# Adafruit_SHT4x_Trinkey.net
KiCad netlist of a schematic drawn in EAGLE
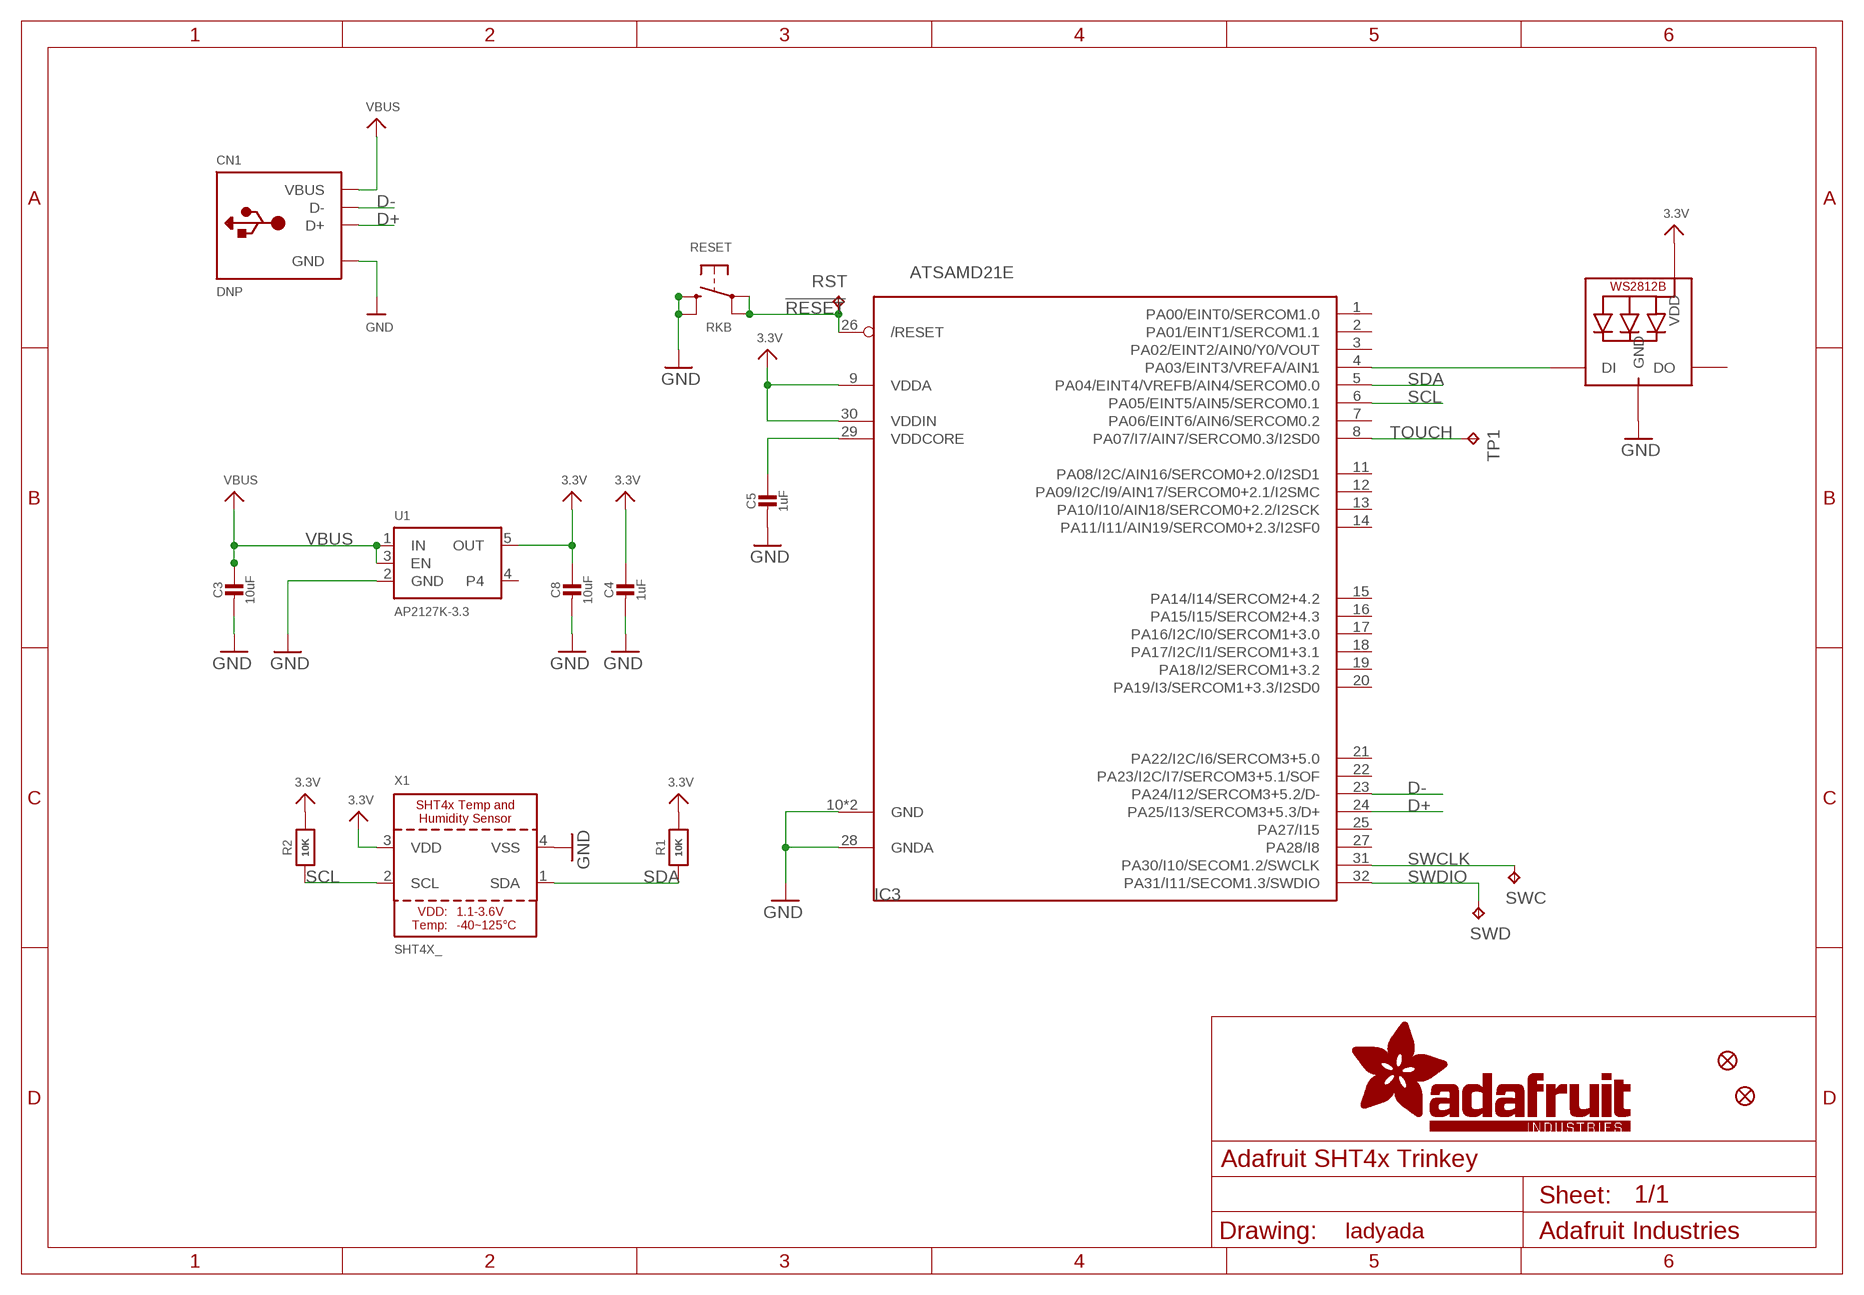
[diagram p0: schematic, sheet 1]

(export (version "E")
  (design (tool "Eeschema 10.0.6"))
  (components
    (comp (ref "C3")
      (value "10uF")
      (footprint "eagle-import:0805-NO")
      (libsource (lib "eagle-import") (part "CAP_CERAMIC0805-NOOUTLINE"))
    )
    (comp (ref "C4")
      (value "1uF")
      (footprint "eagle-import:_0603MP")
      (libsource (lib "eagle-import") (part "CAP_CERAMIC_0603MP"))
    )
    (comp (ref "C5")
      (value "1uF")
      (footprint "eagle-import:0603-NO")
      (libsource (lib "eagle-import") (part "CAP_CERAMIC0603_NO"))
    )
    (comp (ref "C8")
      (value "10uF")
      (footprint "eagle-import:0805-NO")
      (libsource (lib "eagle-import") (part "CAP_CERAMIC0805-NOOUTLINE"))
    )
    (comp (ref "CN1")
      (value "DNP")
      (footprint "eagle-import:USBA_PCB")
      (libsource (lib "eagle-import") (part "USB_TYPEAPCB"))
    )
    (comp (ref "FID1")
      (value "FIDUCIAL_0.5MM")
      (footprint "eagle-import:FIDUCIAL_0.5MM")
      (libsource (lib "eagle-import") (part "FIDUCIAL_0.5MM"))
    )
    (comp (ref "FID2")
      (value "FIDUCIAL_0.5MM")
      (footprint "eagle-import:FIDUCIAL_0.5MM")
      (libsource (lib "eagle-import") (part "FIDUCIAL_0.5MM"))
    )
    (comp (ref "IC3")
      (value "ATSAMD21E")
      (footprint "eagle-import:QFN32_5MM")
      (libsource (lib "eagle-import") (part "ATSAMD21E"))
    )
    (comp (ref "LED1")
      (value "WS2812B_SK6805_1515")
      (footprint "eagle-import:SK6805_1515")
      (libsource (lib "eagle-import") (part "WS2812B_SK6805_1515"))
    )
    (comp (ref "R1")
      (value "10K")
      (footprint "eagle-import:_0402NO")
      (libsource (lib "eagle-import") (part "RESISTOR_0402NO"))
    )
    (comp (ref "R2")
      (value "10K")
      (footprint "eagle-import:_0402NO")
      (libsource (lib "eagle-import") (part "RESISTOR_0402NO"))
    )
    (comp (ref "RESET")
      (value "RKB")
      (footprint "eagle-import:BTN_RKB2_4.6X2.8")
      (libsource (lib "eagle-import") (part "SWITCH_TACT_SMT_RKB2"))
    )
    (comp (ref "RST")
      (value "TPTP16R")
      (footprint "eagle-import:TP16R")
      (libsource (lib "eagle-import") (part "TPTP16R"))
    )
    (comp (ref "SWC")
      (value "TPTP15R")
      (footprint "eagle-import:TP15R")
      (libsource (lib "eagle-import") (part "TPTP15R"))
    )
    (comp (ref "SWD")
      (value "TPTP16R")
      (footprint "eagle-import:TP16R")
      (libsource (lib "eagle-import") (part "TPTP16R"))
    )
    (comp (ref "TP1")
      (value "DNP")
      (footprint "eagle-import:TP13R")
      (libsource (lib "eagle-import") (part "TPTP13R"))
    )
    (comp (ref "U1")
      (value "AP2127K-3.3")
      (footprint "eagle-import:SOT23-5")
      (fields (field (name "JLC_ROTATION") "0"))
      (libsource (lib "eagle-import") (part "VREG_SOT23-5"))
    )
    (comp (ref "X1")
      (value "SHT4X_")
      (footprint "eagle-import:SHT4X")
      (libsource (lib "eagle-import") (part "SHT4X_"))
    )
  )
  (nets
    (net (code "1") (name "/D+") (class "Default")
      (node (ref "CN1") (pin "USB_PLUS") (pinfunction "D+_USB_PLUS") (pintype "bidirectional"))
      (node (ref "IC3") (pin "24") (pinfunction "PA25/I13/SERCOM3+5.3/D+_24") (pintype "bidirectional"))
    )
    (net (code "2") (name "/D-") (class "Default")
      (node (ref "CN1") (pin "USB_NEG") (pinfunction "D-_USB_NEG") (pintype "bidirectional"))
      (node (ref "IC3") (pin "23") (pinfunction "PA24/I12/SERCOM3+5.2/D-_23") (pintype "bidirectional"))
    )
    (net (code "3") (name "/SCL") (class "Default")
      (node (ref "IC3") (pin "6") (pinfunction "PA05/EINT5/AIN5/SERCOM0.1_6") (pintype "bidirectional"))
      (node (ref "R2") (pin "1") (pinfunction "1_1") (pintype "passive"))
      (node (ref "X1") (pin "2") (pinfunction "SCL_2") (pintype "bidirectional"))
    )
    (net (code "4") (name "/SDA") (class "Default")
      (node (ref "IC3") (pin "5") (pinfunction "PA04/EINT4/VREFB/AIN4/SERCOM0.0_5") (pintype "bidirectional"))
      (node (ref "R1") (pin "1") (pinfunction "1_1") (pintype "passive"))
      (node (ref "X1") (pin "1") (pinfunction "SDA_1") (pintype "bidirectional"))
    )
    (net (code "5") (name "/SWCLK") (class "Default")
      (node (ref "IC3") (pin "31") (pinfunction "PA30/I10/SECOM1.2/SWCLK_31") (pintype "bidirectional"))
      (node (ref "SWC") (pin "TP") (pinfunction "TP_TP") (pintype "input"))
    )
    (net (code "6") (name "/SWDIO") (class "Default")
      (node (ref "IC3") (pin "32") (pinfunction "PA31/I11/SECOM1.3/SWDIO_32") (pintype "bidirectional"))
      (node (ref "SWD") (pin "TP") (pinfunction "TP_TP") (pintype "input"))
    )
    (net (code "7") (name "/TOUCH") (class "Default")
      (node (ref "IC3") (pin "8") (pinfunction "PA07/I7/AIN7/SERCOM0.3/I2SD0_8") (pintype "bidirectional"))
      (node (ref "TP1") (pin "TP") (pinfunction "TP_TP") (pintype "input"))
    )
    (net (code "8") (name "/~{RESET}") (class "Default")
      (node (ref "IC3") (pin "26") (pinfunction "/RESET_26") (pintype "bidirectional"))
      (node (ref "RESET") (pin "A") (pinfunction "P_A") (pintype "passive"))
      (node (ref "RESET") (pin "A'") (pinfunction "P1_A'") (pintype "passive"))
      (node (ref "RST") (pin "TP") (pinfunction "TP_TP") (pintype "input"))
    )
    (net (code "9") (name "3.3V") (class "Default")
      (node (ref "C4") (pin "1") (pinfunction "1_1") (pintype "passive"))
      (node (ref "C8") (pin "1") (pinfunction "1_1") (pintype "passive"))
      (node (ref "IC3") (pin "30") (pinfunction "VDDIN_30") (pintype "power_in"))
      (node (ref "IC3") (pin "9") (pinfunction "VDDA_9") (pintype "power_in"))
      (node (ref "LED1") (pin "2") (pinfunction "VDD_2") (pintype "power_in"))
      (node (ref "R1") (pin "2") (pinfunction "2_2") (pintype "passive"))
      (node (ref "R2") (pin "2") (pinfunction "2_2") (pintype "passive"))
      (node (ref "U1") (pin "5") (pinfunction "OUT_5") (pintype "power_in"))
      (node (ref "X1") (pin "3") (pinfunction "VDD_3") (pintype "power_in"))
    )
    (net (code "10") (name "GND") (class "Default")
      (node (ref "C3") (pin "2") (pinfunction "2_2") (pintype "passive"))
      (node (ref "C4") (pin "2") (pinfunction "2_2") (pintype "passive"))
      (node (ref "C5") (pin "2") (pinfunction "2_2") (pintype "passive"))
      (node (ref "C8") (pin "2") (pinfunction "2_2") (pintype "passive"))
      (node (ref "CN1") (pin "GND") (pinfunction "GND_GND") (pintype "power_in"))
      (node (ref "IC3") (pin "10") (pinfunction "GND_10") (pintype "power_in"))
      (node (ref "IC3") (pin "28") (pinfunction "GNDA_28") (pintype "power_in"))
      (node (ref "IC3") (pin "33") (pinfunction "GND_33") (pintype "power_in"))
      (node (ref "LED1") (pin "4") (pinfunction "GND_4") (pintype "power_in"))
      (node (ref "RESET") (pin "B") (pinfunction "S_B") (pintype "passive"))
      (node (ref "RESET") (pin "B'") (pinfunction "S1_B'") (pintype "passive"))
      (node (ref "U1") (pin "2") (pinfunction "GND_2") (pintype "power_in"))
      (node (ref "X1") (pin "4") (pinfunction "VSS_4") (pintype "power_in"))
    )
    (net (code "11") (name "Net-(IC3-PA03{slash}EINT3{slash}VREFA{slash}AIN1)") (class "Default")
      (node (ref "IC3") (pin "4") (pinfunction "PA03/EINT3/VREFA/AIN1_4") (pintype "bidirectional"))
      (node (ref "LED1") (pin "1") (pinfunction "DI_1") (pintype "input"))
    )
    (net (code "12") (name "Net-(IC3-VDDCORE)") (class "Default")
      (node (ref "C5") (pin "1") (pinfunction "1_1") (pintype "passive"))
      (node (ref "IC3") (pin "29") (pinfunction "VDDCORE_29") (pintype "power_in"))
    )
    (net (code "13") (name "VBUS") (class "Default")
      (node (ref "C3") (pin "1") (pinfunction "1_1") (pintype "passive"))
      (node (ref "CN1") (pin "VCC") (pinfunction "VBUS_VCC") (pintype "power_in"))
      (node (ref "U1") (pin "1") (pinfunction "IN_1") (pintype "power_in"))
      (node (ref "U1") (pin "3") (pinfunction "EN_3") (pintype "input"))
    )
    (net (code "14") (name "unconnected-(IC3-PA00{slash}EINT0{slash}SERCOM1.0-Pad1)") (class "Default")
      (node (ref "IC3") (pin "1") (pinfunction "PA00/EINT0/SERCOM1.0_1") (pintype "bidirectional"))
    )
    (net (code "15") (name "unconnected-(IC3-PA01{slash}EINT1{slash}SERCOM1.1-Pad2)") (class "Default")
      (node (ref "IC3") (pin "2") (pinfunction "PA01/EINT1/SERCOM1.1_2") (pintype "bidirectional"))
    )
    (net (code "16") (name "unconnected-(IC3-PA02{slash}EINT2{slash}AIN0{slash}Y0{slash}VOUT-Pad3)") (class "Default")
      (node (ref "IC3") (pin "3") (pinfunction "PA02/EINT2/AIN0/Y0/VOUT_3") (pintype "bidirectional"))
    )
    (net (code "17") (name "unconnected-(IC3-PA06{slash}EINT6{slash}AIN6{slash}SERCOM0.2-Pad7)") (class "Default")
      (node (ref "IC3") (pin "7") (pinfunction "PA06/EINT6/AIN6/SERCOM0.2_7") (pintype "bidirectional"))
    )
    (net (code "18") (name "unconnected-(IC3-PA08{slash}I2C{slash}AIN16{slash}SERCOM0+2.0{slash}I2SD1-Pad11)") (class "Default")
      (node (ref "IC3") (pin "11") (pinfunction "PA08/I2C/AIN16/SERCOM0+2.0/I2SD1_11") (pintype "bidirectional"))
    )
    (net (code "19") (name "unconnected-(IC3-PA09{slash}I2C{slash}I9{slash}AIN17{slash}SERCOM0+2.1{slash}I2SMC-Pad12)") (class "Default")
      (node (ref "IC3") (pin "12") (pinfunction "PA09/I2C/I9/AIN17/SERCOM0+2.1/I2SMC_12") (pintype "bidirectional"))
    )
    (net (code "20") (name "unconnected-(IC3-PA10{slash}I10{slash}AIN18{slash}SERCOM0+2.2{slash}I2SCK-Pad13)") (class "Default")
      (node (ref "IC3") (pin "13") (pinfunction "PA10/I10/AIN18/SERCOM0+2.2/I2SCK_13") (pintype "bidirectional"))
    )
    (net (code "21") (name "unconnected-(IC3-PA11{slash}I11{slash}AIN19{slash}SERCOM0+2.3{slash}I2SF0-Pad14)") (class "Default")
      (node (ref "IC3") (pin "14") (pinfunction "PA11/I11/AIN19/SERCOM0+2.3/I2SF0_14") (pintype "bidirectional"))
    )
    (net (code "22") (name "unconnected-(IC3-PA14{slash}I14{slash}SERCOM2+4.2-Pad15)") (class "Default")
      (node (ref "IC3") (pin "15") (pinfunction "PA14/I14/SERCOM2+4.2_15") (pintype "bidirectional"))
    )
    (net (code "23") (name "unconnected-(IC3-PA15{slash}I15{slash}SERCOM2+4.3-Pad16)") (class "Default")
      (node (ref "IC3") (pin "16") (pinfunction "PA15/I15/SERCOM2+4.3_16") (pintype "bidirectional"))
    )
    (net (code "24") (name "unconnected-(IC3-PA16{slash}I2C{slash}I0{slash}SERCOM1+3.0-Pad17)") (class "Default")
      (node (ref "IC3") (pin "17") (pinfunction "PA16/I2C/I0/SERCOM1+3.0_17") (pintype "bidirectional"))
    )
    (net (code "25") (name "unconnected-(IC3-PA17{slash}I2C{slash}I1{slash}SERCOM1+3.1-Pad18)") (class "Default")
      (node (ref "IC3") (pin "18") (pinfunction "PA17/I2C/I1/SERCOM1+3.1_18") (pintype "bidirectional"))
    )
    (net (code "26") (name "unconnected-(IC3-PA18{slash}I2{slash}SERCOM1+3.2-Pad19)") (class "Default")
      (node (ref "IC3") (pin "19") (pinfunction "PA18/I2/SERCOM1+3.2_19") (pintype "bidirectional"))
    )
    (net (code "27") (name "unconnected-(IC3-PA19{slash}I3{slash}SERCOM1+3.3{slash}I2SD0-Pad20)") (class "Default")
      (node (ref "IC3") (pin "20") (pinfunction "PA19/I3/SERCOM1+3.3/I2SD0_20") (pintype "bidirectional"))
    )
    (net (code "28") (name "unconnected-(IC3-PA22{slash}I2C{slash}I6{slash}SERCOM3+5.0-Pad21)") (class "Default")
      (node (ref "IC3") (pin "21") (pinfunction "PA22/I2C/I6/SERCOM3+5.0_21") (pintype "bidirectional"))
    )
    (net (code "29") (name "unconnected-(IC3-PA23{slash}I2C{slash}I7{slash}SERCOM3+5.1{slash}SOF-Pad22)") (class "Default")
      (node (ref "IC3") (pin "22") (pinfunction "PA23/I2C/I7/SERCOM3+5.1/SOF_22") (pintype "bidirectional"))
    )
    (net (code "30") (name "unconnected-(IC3-PA27{slash}I15-Pad25)") (class "Default")
      (node (ref "IC3") (pin "25") (pinfunction "PA27/I15_25") (pintype "bidirectional"))
    )
    (net (code "31") (name "unconnected-(IC3-PA28{slash}I8-Pad27)") (class "Default")
      (node (ref "IC3") (pin "27") (pinfunction "PA28/I8_27") (pintype "bidirectional"))
    )
    (net (code "32") (name "unconnected-(LED1-DO-Pad3)") (class "Default")
      (node (ref "LED1") (pin "3") (pinfunction "DO_3") (pintype "output"))
    )
    (net (code "33") (name "unconnected-(U1-P4-Pad4)") (class "Default")
      (node (ref "U1") (pin "4") (pinfunction "P4_4") (pintype "bidirectional"))
    )
  )
)
